# VCA821_PGA.net
KiCad netlist of a schematic drawn in Altium Designer
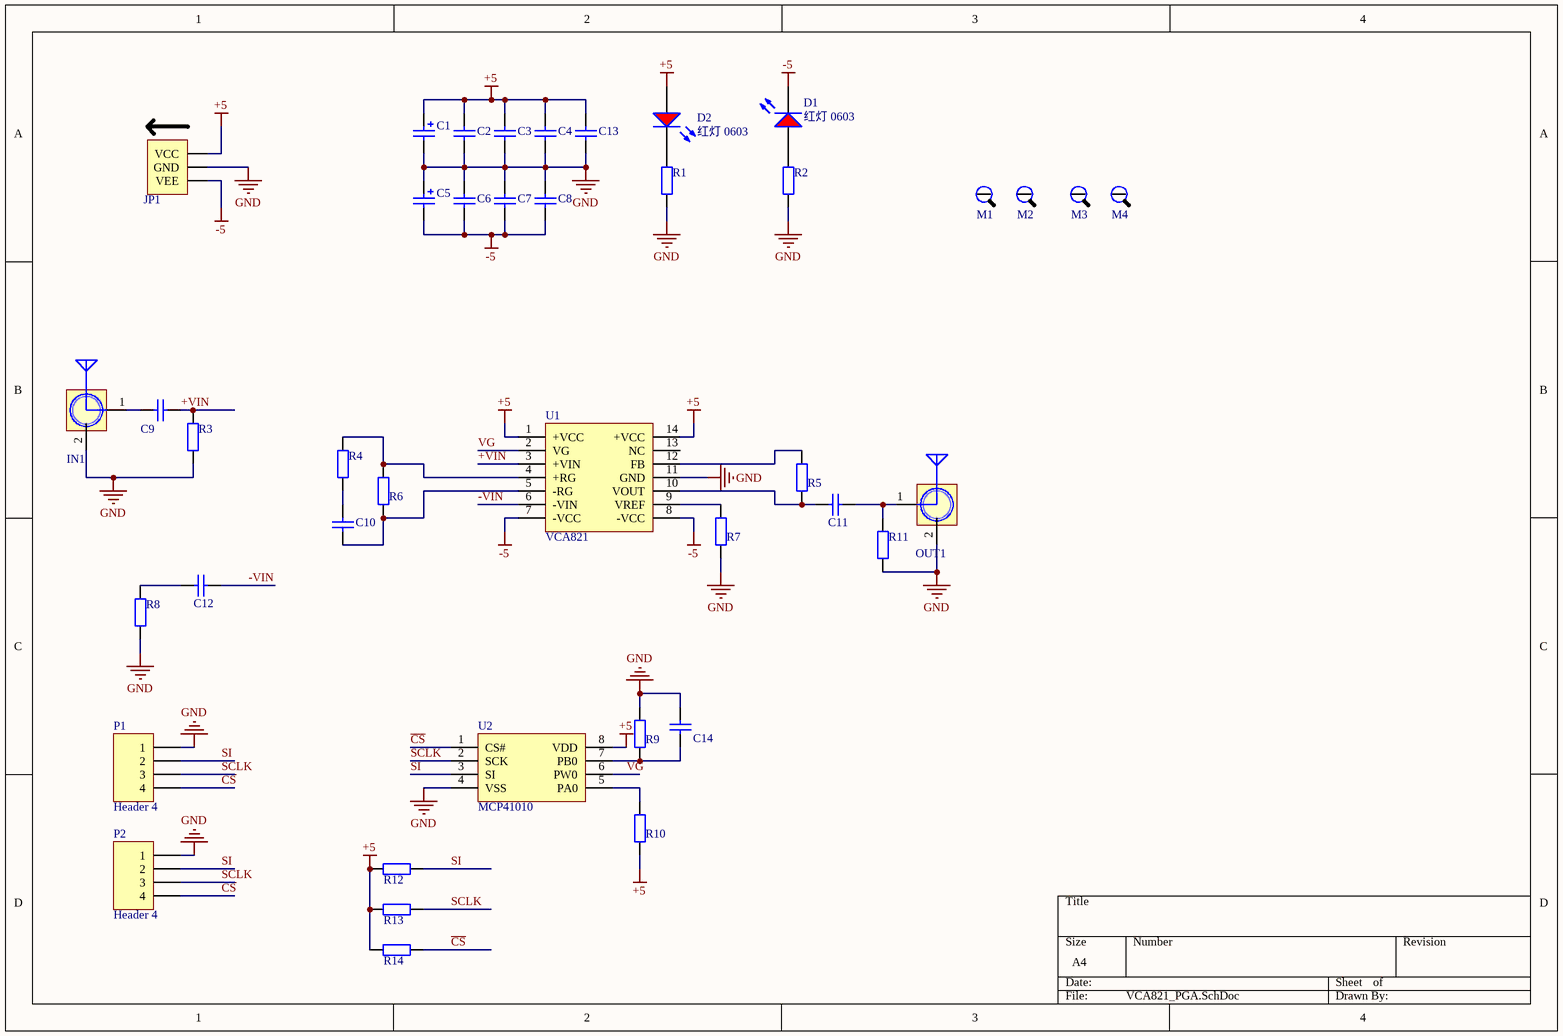
[diagram p0: VCA821_PGA.SchDoc]

(export (version "E")
  (design (tool "Eeschema 10.0.6"))
  (components
    (comp (ref "C1")
      (value "10uF (106) ±10% 16V")
      (footprint "CASE-A_3216")
      (description "钽电容")
      (libsource (lib "JLC") (part "3216 10uF (106) 10% 16V"))
    )
    (comp (ref "C2")
      (value "100nF (104) 10% 50V")
      (footprint "0603_C")
      (description "贴片电容")
      (libsource (lib "JLC") (part "0603 100nF (104) 10% 50V"))
    )
    (comp (ref "C3")
      (value "100nF (104) 10% 50V")
      (footprint "0603_C")
      (description "贴片电容")
      (libsource (lib "JLC") (part "0603 100nF (104) 10% 50V"))
    )
    (comp (ref "C4")
      (value "100nF (104) 10% 50V")
      (footprint "0603_C")
      (description "贴片电容")
      (libsource (lib "JLC") (part "0603 100nF (104) 10% 50V"))
    )
    (comp (ref "C5")
      (value "10uF (106) ±10% 16V")
      (footprint "CASE-A_3216")
      (description "钽电容")
      (libsource (lib "JLC") (part "3216 10uF (106) 10% 16V"))
    )
    (comp (ref "C6")
      (value "100nF (104) 10% 50V")
      (footprint "0603_C")
      (description "贴片电容")
      (libsource (lib "JLC") (part "0603 100nF (104) 10% 50V"))
    )
    (comp (ref "C7")
      (value "100nF (104) 10% 50V")
      (footprint "0603_C")
      (description "贴片电容")
      (libsource (lib "JLC") (part "0603 100nF (104) 10% 50V"))
    )
    (comp (ref "C8")
      (value "100nF (104) 10% 50V")
      (footprint "0603_C")
      (description "贴片电容")
      (libsource (lib "JLC") (part "0603 100nF (104) 10% 50V"))
    )
    (comp (ref "C9")
      (value "100nF (104) 10% 50V")
      (footprint "0603_C")
      (description "贴片电容")
      (libsource (lib "JLC") (part "0603 100nF (104) 10% 50V"))
    )
    (comp (ref "C10")
      (value "100nF (104) 10% 50V")
      (footprint "0603_C")
      (description "贴片电容")
      (libsource (lib "JLC") (part "0603 100nF (104) 10% 50V"))
    )
    (comp (ref "C11")
      (value "100nF (104) 10% 50V")
      (footprint "0603_C")
      (description "贴片电容")
      (libsource (lib "JLC") (part "0603 100nF (104) 10% 50V"))
    )
    (comp (ref "C12")
      (value "100nF (104) 10% 50V")
      (footprint "0603_C")
      (description "贴片电容")
      (libsource (lib "JLC") (part "0603 100nF (104) 10% 50V"))
    )
    (comp (ref "C13")
      (value "100nF (104) 10% 50V")
      (footprint "0603_C")
      (description "贴片电容")
      (libsource (lib "JLC") (part "0603 100nF (104) 10% 50V"))
    )
    (comp (ref "C14")
      (value "100nF (104) 10% 50V")
      (footprint "0603_C")
      (description "贴片电容")
      (libsource (lib "JLC") (part "0603 100nF (104) 10% 50V"))
    )
    (comp (ref "D1")
      (value "红灯 0603")
      (footprint "0603_LED_S1")
      (description "发光二极管")
      (libsource (lib "JLC") (part "0603 红灯"))
    )
    (comp (ref "D2")
      (value "红灯 0603")
      (footprint "0603_LED_S1")
      (description "发光二极管")
      (libsource (lib "JLC") (part "0603 红灯"))
    )
    (comp (ref "IN1")
      (value "SMA WIFI 天线接口")
      (footprint "SMA")
      (description "SMA-2.4G射频天线接口")
      (fields (field (name "版权归属") "源创客"))
      (libsource (lib "Cooperation") (part "PORT_SMA"))
    )
    (comp (ref "JP1")
      (value "HDR-1X3")
      (footprint "Power_IN_3.81-3P")
      (description "3P接插件,模块双电源供电口")
      (fields (field (name "版权归属") "源创客"))
      (libsource (lib "Cooperation") (part "PORT_Power_IN3"))
    )
    (comp (ref "M1")
      (value "M3")
      (footprint "M3x10_L")
      (description "螺丝")
      (libsource (lib "Cooperation") (part "ELSE_M3_screw"))
    )
    (comp (ref "M2")
      (value "M3")
      (footprint "M3x10_L")
      (description "螺丝")
      (libsource (lib "Cooperation") (part "ELSE_M3_screw"))
    )
    (comp (ref "M3")
      (value "M3")
      (footprint "M3x10_L")
      (description "螺丝")
      (libsource (lib "Cooperation") (part "ELSE_M3_screw"))
    )
    (comp (ref "M4")
      (value "M3")
      (footprint "M3x10_L")
      (description "螺丝")
      (libsource (lib "Cooperation") (part "ELSE_M3_screw"))
    )
    (comp (ref "OUT1")
      (value "SMA WIFI 天线接口")
      (footprint "SMA")
      (description "SMA-2.4G射频天线接口")
      (fields (field (name "版权归属") "源创客"))
      (libsource (lib "") (part "PORT_SMA_1"))
    )
    (comp (ref "P1")
      (value "Header 4")
      (footprint "MX 1.25-WS-4P")
      (description "Header, 4-Pin")
      (fields (field (name "PUBLISHER") "Altium Limited"))
      (libsource (lib "Miscellaneous Connectors") (part "Header 4"))
    )
    (comp (ref "P2")
      (value "Header 4")
      (footprint "HDR1X4")
      (description "Header, 4-Pin")
      (fields (field (name "PUBLISHER") "Altium Limited"))
      (libsource (lib "Miscellaneous Connectors") (part "Header 4"))
    )
    (comp (ref "R1")
      (value "10KΩ (1002) ±1%")
      (footprint "0603_R")
      (description "贴片电阻")
      (libsource (lib "JLC") (part "0603 10KΩ (1002) 1%"))
    )
    (comp (ref "R2")
      (value "10KΩ (1002) ±1%")
      (footprint "0603_R")
      (description "贴片电阻")
      (libsource (lib "JLC") (part "0603 10KΩ (1002) 1%"))
    )
    (comp (ref "R3")
      (value "10KΩ (1002) ±1%")
      (footprint "0603_R")
      (description "贴片电阻")
      (libsource (lib "JLC") (part "0603 10KΩ (1002) 1%"))
    )
    (comp (ref "R4")
      (value "10KΩ (1002) ±1%")
      (footprint "0603_R")
      (description "贴片电阻")
      (libsource (lib "JLC") (part "0603 10KΩ (1002) 1%"))
    )
    (comp (ref "R5")
      (value "10KΩ (1002) ±1%")
      (footprint "0603_R")
      (description "贴片电阻")
      (libsource (lib "") (part "0603 10KΩ (1002) 1%_2"))
    )
    (comp (ref "R6")
      (value "10KΩ (1002) ±1%")
      (footprint "0603_R")
      (description "贴片电阻")
      (libsource (lib "") (part "0603 10KΩ (1002) 1%_2"))
    )
    (comp (ref "R7")
      (value "10KΩ (1002) ±1%")
      (footprint "0603_R")
      (description "贴片电阻")
      (libsource (lib "") (part "0603 10KΩ (1002) 1%_2"))
    )
    (comp (ref "R8")
      (value "10KΩ (1002) ±1%")
      (footprint "0603_R")
      (description "贴片电阻")
      (libsource (lib "JLC") (part "0603 10KΩ (1002) 1%"))
    )
    (comp (ref "R9")
      (value "10KΩ (1002) ±1%")
      (footprint "0603_R")
      (description "贴片电阻")
      (libsource (lib "") (part "0603 10KΩ (1002) 1%_2"))
    )
    (comp (ref "R10")
      (value "10KΩ (1002) ±1%")
      (footprint "0603_R")
      (description "贴片电阻")
      (libsource (lib "") (part "0603 10KΩ (1002) 1%_2"))
    )
    (comp (ref "R11")
      (value "10KΩ (1002) ±1%")
      (footprint "0603_R")
      (description "贴片电阻")
      (libsource (lib "JLC") (part "0603 10KΩ (1002) 1%"))
    )
    (comp (ref "R12")
      (value "10KΩ (1002) ±1%")
      (footprint "0603_R")
      (description "贴片电阻")
      (libsource (lib "") (part "0603 10KΩ (1002) 1%_1"))
    )
    (comp (ref "R13")
      (value "10KΩ (1002) ±1%")
      (footprint "0603_R")
      (description "贴片电阻")
      (libsource (lib "") (part "0603 10KΩ (1002) 1%_1"))
    )
    (comp (ref "R14")
      (value "10KΩ (1002) ±1%")
      (footprint "0603_R")
      (description "贴片电阻")
      (libsource (lib "") (part "0603 10KΩ (1002) 1%_1"))
    )
    (comp (ref "U1") (value "VCA821") (footprint "SO-14N") (libsource (lib "Cooperation") (part "VCA821")))
    (comp (ref "U2")
      (value "MCP41010")
      (footprint "SOIC-8")
      (libsource (lib "Cooperation") (part "IC_MCP41010T"))
    )
  )
  (nets
    (net (code "1") (name "+5") (class "Default")
      (node (ref "C1") (pin "1") (pinfunction "1_1") (pintype "passive"))
      (node (ref "C13") (pin "2") (pinfunction "2_2") (pintype "passive"))
      (node (ref "C2") (pin "2") (pinfunction "2_2") (pintype "passive"))
      (node (ref "C3") (pin "2") (pinfunction "2_2") (pintype "passive"))
      (node (ref "C4") (pin "2") (pinfunction "2_2") (pintype "passive"))
      (node (ref "D2") (pin "A") (pinfunction "A_A") (pintype "passive"))
      (node (ref "JP1") (pin "1") (pinfunction "VCC_1") (pintype "passive"))
      (node (ref "R10") (pin "2") (pinfunction "2_2") (pintype "passive"))
      (node (ref "R12") (pin "1") (pinfunction "1_1") (pintype "passive"))
      (node (ref "R13") (pin "1") (pinfunction "1_1") (pintype "passive"))
      (node (ref "R14") (pin "1") (pinfunction "1_1") (pintype "passive"))
      (node (ref "U1") (pin "1") (pinfunction "+VCC_1") (pintype "passive"))
      (node (ref "U1") (pin "14") (pinfunction "+VCC_14") (pintype "passive"))
      (node (ref "U2") (pin "8") (pinfunction "VDD_8") (pintype "passive"))
    )
    (net (code "2") (name "-5") (class "Default")
      (node (ref "C5") (pin "2") (pinfunction "2_2") (pintype "passive"))
      (node (ref "C6") (pin "1") (pinfunction "1_1") (pintype "passive"))
      (node (ref "C7") (pin "1") (pinfunction "1_1") (pintype "passive"))
      (node (ref "C8") (pin "1") (pinfunction "1_1") (pintype "passive"))
      (node (ref "D1") (pin "K") (pinfunction "K_K") (pintype "passive"))
      (node (ref "JP1") (pin "3") (pinfunction "VEE_3") (pintype "passive"))
      (node (ref "U1") (pin "7") (pinfunction "-VCC_7") (pintype "passive"))
      (node (ref "U1") (pin "8") (pinfunction "-VCC_8") (pintype "passive"))
    )
    (net (code "3") (name "/+VIN") (class "Default")
      (node (ref "C9") (pin "1") (pinfunction "1_1") (pintype "passive"))
      (node (ref "R3") (pin "2") (pinfunction "2_2") (pintype "passive"))
      (node (ref "U1") (pin "3") (pinfunction "+VIN_3") (pintype "passive"))
    )
    (net (code "4") (name "/-VIN") (class "Default")
      (node (ref "C12") (pin "1") (pinfunction "1_1") (pintype "passive"))
      (node (ref "U1") (pin "6") (pinfunction "-VIN_6") (pintype "passive"))
    )
    (net (code "5") (name "/SCLK") (class "Default")
      (node (ref "P1") (pin "3") (pinfunction "3_3") (pintype "passive"))
      (node (ref "P2") (pin "3") (pinfunction "3_3") (pintype "passive"))
      (node (ref "R13") (pin "2") (pinfunction "2_2") (pintype "passive"))
      (node (ref "U2") (pin "2") (pinfunction "SCK_2") (pintype "passive"))
    )
    (net (code "6") (name "/SI") (class "Default")
      (node (ref "P1") (pin "2") (pinfunction "2_2") (pintype "passive"))
      (node (ref "P2") (pin "2") (pinfunction "2_2") (pintype "passive"))
      (node (ref "R12") (pin "2") (pinfunction "2_2") (pintype "passive"))
      (node (ref "U2") (pin "3") (pinfunction "SI_3") (pintype "passive"))
    )
    (net (code "7") (name "/VG") (class "Default")
      (node (ref "U1") (pin "2") (pinfunction "VG_2") (pintype "passive"))
      (node (ref "U2") (pin "6") (pinfunction "PW0_6") (pintype "passive"))
    )
    (net (code "8") (name "/~{CS}") (class "Default")
      (node (ref "P1") (pin "4") (pinfunction "4_4") (pintype "passive"))
      (node (ref "P2") (pin "4") (pinfunction "4_4") (pintype "passive"))
      (node (ref "R14") (pin "2") (pinfunction "2_2") (pintype "passive"))
      (node (ref "U2") (pin "1") (pinfunction "CS#_1") (pintype "passive"))
    )
    (net (code "9") (name "GND") (class "Default")
      (node (ref "C1") (pin "2") (pinfunction "2_2") (pintype "passive"))
      (node (ref "C13") (pin "1") (pinfunction "1_1") (pintype "passive"))
      (node (ref "C14") (pin "1") (pinfunction "1_1") (pintype "passive"))
      (node (ref "C2") (pin "1") (pinfunction "1_1") (pintype "passive"))
      (node (ref "C3") (pin "1") (pinfunction "1_1") (pintype "passive"))
      (node (ref "C4") (pin "1") (pinfunction "1_1") (pintype "passive"))
      (node (ref "C5") (pin "1") (pinfunction "1_1") (pintype "passive"))
      (node (ref "C6") (pin "2") (pinfunction "2_2") (pintype "passive"))
      (node (ref "C7") (pin "2") (pinfunction "2_2") (pintype "passive"))
      (node (ref "C8") (pin "2") (pinfunction "2_2") (pintype "passive"))
      (node (ref "IN1") (pin "2") (pinfunction "2_2") (pintype "passive"))
      (node (ref "JP1") (pin "2") (pinfunction "GND_2") (pintype "passive"))
      (node (ref "OUT1") (pin "2") (pinfunction "2_2") (pintype "passive"))
      (node (ref "P1") (pin "1") (pinfunction "1_1") (pintype "passive"))
      (node (ref "P2") (pin "1") (pinfunction "1_1") (pintype "passive"))
      (node (ref "R1") (pin "1") (pinfunction "1_1") (pintype "passive"))
      (node (ref "R11") (pin "1") (pinfunction "1_1") (pintype "passive"))
      (node (ref "R2") (pin "1") (pinfunction "1_1") (pintype "passive"))
      (node (ref "R3") (pin "1") (pinfunction "1_1") (pintype "passive"))
      (node (ref "R7") (pin "2") (pinfunction "2_2") (pintype "passive"))
      (node (ref "R8") (pin "1") (pinfunction "1_1") (pintype "passive"))
      (node (ref "R9") (pin "1") (pinfunction "1_1") (pintype "passive"))
      (node (ref "U1") (pin "11") (pinfunction "GND_11") (pintype "passive"))
      (node (ref "U2") (pin "4") (pinfunction "VSS_4") (pintype "passive"))
    )
    (net (code "10") (name "Net-(C10-Pad2)") (class "Default")
      (node (ref "C10") (pin "2") (pinfunction "2_2") (pintype "passive"))
      (node (ref "R4") (pin "1") (pinfunction "1_1") (pintype "passive"))
    )
    (net (code "11") (name "Net-(C12-Pad2)") (class "Default")
      (node (ref "C12") (pin "2") (pinfunction "2_2") (pintype "passive"))
      (node (ref "R8") (pin "2") (pinfunction "2_2") (pintype "passive"))
    )
    (net (code "12") (name "Net-(D1-PadA)") (class "Default")
      (node (ref "D1") (pin "A") (pinfunction "A_A") (pintype "passive"))
      (node (ref "R2") (pin "2") (pinfunction "2_2") (pintype "passive"))
    )
    (net (code "13") (name "Net-(D2-PadK)") (class "Default")
      (node (ref "D2") (pin "K") (pinfunction "K_K") (pintype "passive"))
      (node (ref "R1") (pin "2") (pinfunction "2_2") (pintype "passive"))
    )
    (net (code "14") (name "Net-(IN1-SINGLE)") (class "Default")
      (node (ref "C9") (pin "2") (pinfunction "2_2") (pintype "passive"))
      (node (ref "IN1") (pin "1") (pinfunction "SINGLE_1") (pintype "passive"))
    )
    (net (code "15") (name "Net-(OUT1-SINGLE)") (class "Default")
      (node (ref "C11") (pin "1") (pinfunction "1_1") (pintype "passive"))
      (node (ref "OUT1") (pin "1") (pinfunction "SINGLE_1") (pintype "passive"))
      (node (ref "R11") (pin "2") (pinfunction "2_2") (pintype "passive"))
    )
    (net (code "16") (name "Net-(U1-+RG)") (class "Default")
      (node (ref "R4") (pin "2") (pinfunction "2_2") (pintype "passive"))
      (node (ref "R6") (pin "1") (pinfunction "1_1") (pintype "passive"))
      (node (ref "U1") (pin "4") (pinfunction "+RG_4") (pintype "passive"))
    )
    (net (code "17") (name "Net-(U1--RG)") (class "Default")
      (node (ref "C10") (pin "1") (pinfunction "1_1") (pintype "passive"))
      (node (ref "R6") (pin "2") (pinfunction "2_2") (pintype "passive"))
      (node (ref "U1") (pin "5") (pinfunction "-RG_5") (pintype "passive"))
    )
    (net (code "18") (name "Net-(U1-FB)") (class "Default")
      (node (ref "R5") (pin "1") (pinfunction "1_1") (pintype "passive"))
      (node (ref "U1") (pin "12") (pinfunction "FB_12") (pintype "passive"))
    )
    (net (code "19") (name "Net-(U1-VOUT)") (class "Default")
      (node (ref "C11") (pin "2") (pinfunction "2_2") (pintype "passive"))
      (node (ref "R5") (pin "2") (pinfunction "2_2") (pintype "passive"))
      (node (ref "U1") (pin "10") (pinfunction "VOUT_10") (pintype "passive"))
    )
    (net (code "20") (name "Net-(U1-VREF)") (class "Default")
      (node (ref "R7") (pin "1") (pinfunction "1_1") (pintype "passive"))
      (node (ref "U1") (pin "9") (pinfunction "VREF_9") (pintype "passive"))
    )
    (net (code "21") (name "Net-(U2-PA0)") (class "Default")
      (node (ref "R10") (pin "1") (pinfunction "1_1") (pintype "passive"))
      (node (ref "U2") (pin "5") (pinfunction "PA0_5") (pintype "passive"))
    )
    (net (code "22") (name "Net-(U2-PB0)") (class "Default")
      (node (ref "C14") (pin "2") (pinfunction "2_2") (pintype "passive"))
      (node (ref "R9") (pin "2") (pinfunction "2_2") (pintype "passive"))
      (node (ref "U2") (pin "7") (pinfunction "PB0_7") (pintype "passive"))
    )
    (net (code "23") (name "unconnected-(M1-Pad1)") (class "Default")
      (node (ref "M1") (pin "1") (pinfunction "1_1") (pintype "passive"))
    )
    (net (code "24") (name "unconnected-(M2-Pad1)") (class "Default")
      (node (ref "M2") (pin "1") (pinfunction "1_1") (pintype "passive"))
    )
    (net (code "25") (name "unconnected-(M3-Pad1)") (class "Default")
      (node (ref "M3") (pin "1") (pinfunction "1_1") (pintype "passive"))
    )
    (net (code "26") (name "unconnected-(M4-Pad1)") (class "Default")
      (node (ref "M4") (pin "1") (pinfunction "1_1") (pintype "passive"))
    )
    (net (code "27") (name "unconnected-(U1-NC-Pad13)") (class "Default")
      (node (ref "U1") (pin "13") (pinfunction "NC_13") (pintype "passive"))
    )
  )
)
